# lamps.net
KiCad netlist of a schematic drawn in EAGLE
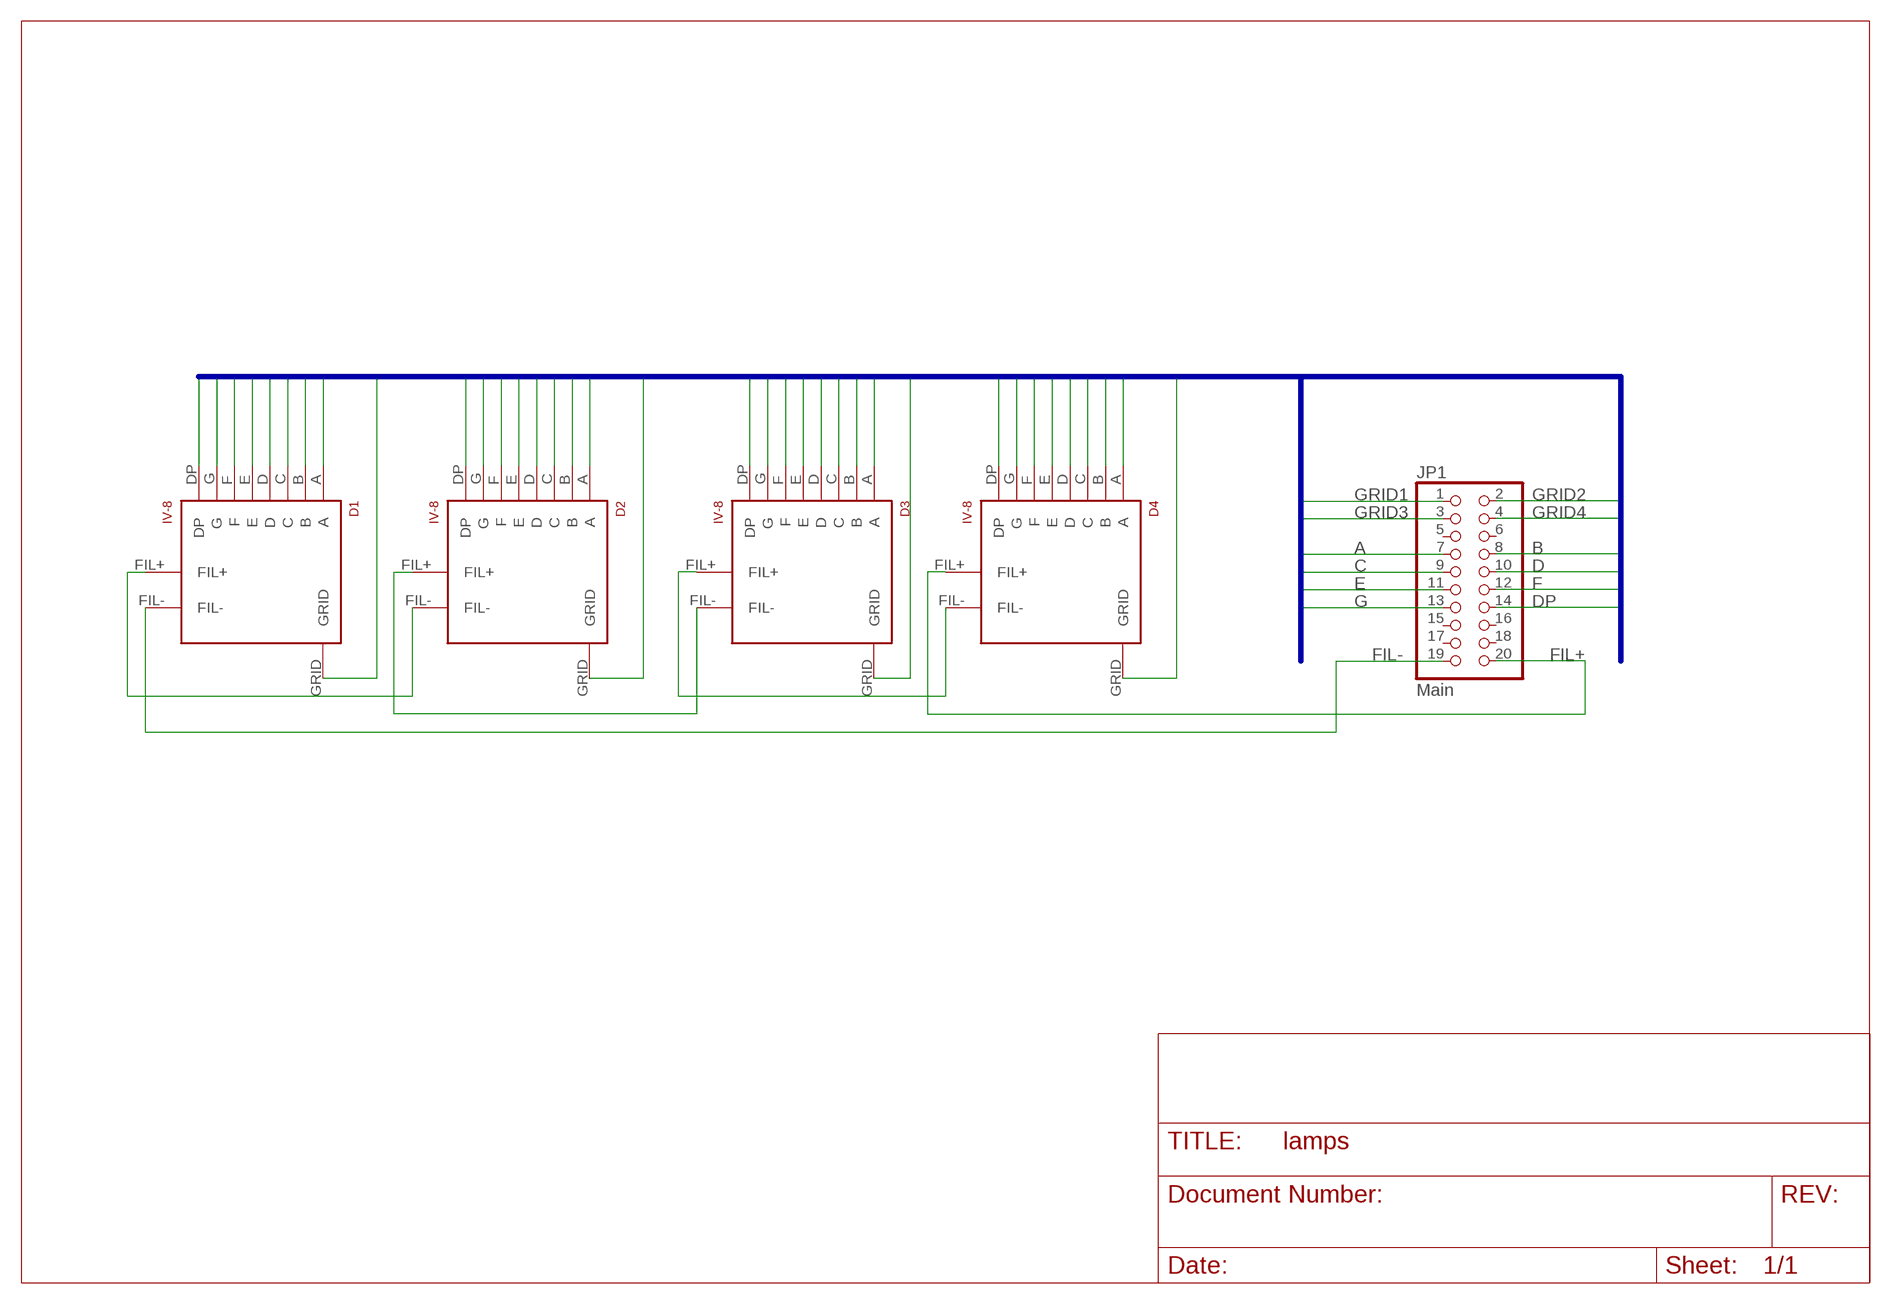
[diagram p0: schematic, sheet 1]

(export (version "E")
  (design (tool "Eeschema 10.0.6"))
  (components
    (comp (ref "D1")
      (value "IV-8")
      (footprint "eagle-import:IV-8")
      (libsource (lib "eagle-import") (part "IV-8"))
    )
    (comp (ref "D2")
      (value "IV-8")
      (footprint "eagle-import:IV-8")
      (libsource (lib "eagle-import") (part "IV-8"))
    )
    (comp (ref "D3")
      (value "IV-8")
      (footprint "eagle-import:IV-8")
      (libsource (lib "eagle-import") (part "IV-8"))
    )
    (comp (ref "D4")
      (value "IV-8")
      (footprint "eagle-import:IV-8")
      (libsource (lib "eagle-import") (part "IV-8"))
    )
    (comp (ref "JP1")
      (value "Main")
      (footprint "eagle-import:2X10")
      (libsource (lib "eagle-import") (part "PINHD-2X10"))
    )
  )
  (nets
    (net (code "1") (name "/A") (class "Default")
      (node (ref "D1") (pin "A") (pinfunction "A_A") (pintype "input"))
      (node (ref "D2") (pin "A") (pinfunction "A_A") (pintype "input"))
      (node (ref "D3") (pin "A") (pinfunction "A_A") (pintype "input"))
      (node (ref "D4") (pin "A") (pinfunction "A_A") (pintype "input"))
      (node (ref "JP1") (pin "7") (pinfunction "A_7") (pintype "passive"))
    )
    (net (code "2") (name "/B") (class "Default")
      (node (ref "D1") (pin "B") (pinfunction "B_B") (pintype "input"))
      (node (ref "D2") (pin "B") (pinfunction "B_B") (pintype "input"))
      (node (ref "D3") (pin "B") (pinfunction "B_B") (pintype "input"))
      (node (ref "D4") (pin "B") (pinfunction "B_B") (pintype "input"))
      (node (ref "JP1") (pin "8") (pinfunction "B_8") (pintype "passive"))
    )
    (net (code "3") (name "/C") (class "Default")
      (node (ref "D1") (pin "C") (pinfunction "C_C") (pintype "bidirectional"))
      (node (ref "D2") (pin "C") (pinfunction "C_C") (pintype "bidirectional"))
      (node (ref "D3") (pin "C") (pinfunction "C_C") (pintype "bidirectional"))
      (node (ref "D4") (pin "C") (pinfunction "C_C") (pintype "bidirectional"))
      (node (ref "JP1") (pin "9") (pinfunction "C_9") (pintype "passive"))
    )
    (net (code "4") (name "/D") (class "Default")
      (node (ref "D1") (pin "D") (pinfunction "D_D") (pintype "input"))
      (node (ref "D2") (pin "D") (pinfunction "D_D") (pintype "input"))
      (node (ref "D3") (pin "D") (pinfunction "D_D") (pintype "input"))
      (node (ref "D4") (pin "D") (pinfunction "D_D") (pintype "input"))
      (node (ref "JP1") (pin "10") (pinfunction "D_10") (pintype "passive"))
    )
    (net (code "5") (name "/DP") (class "Default")
      (node (ref "D1") (pin "DP") (pinfunction "DP_DP") (pintype "bidirectional"))
      (node (ref "D2") (pin "DP") (pinfunction "DP_DP") (pintype "bidirectional"))
      (node (ref "D3") (pin "DP") (pinfunction "DP_DP") (pintype "bidirectional"))
      (node (ref "D4") (pin "DP") (pinfunction "DP_DP") (pintype "bidirectional"))
      (node (ref "JP1") (pin "14") (pinfunction "DP_14") (pintype "passive"))
    )
    (net (code "6") (name "/E") (class "Default")
      (node (ref "D1") (pin "E") (pinfunction "E_E") (pintype "bidirectional"))
      (node (ref "D2") (pin "E") (pinfunction "E_E") (pintype "bidirectional"))
      (node (ref "D3") (pin "E") (pinfunction "E_E") (pintype "bidirectional"))
      (node (ref "D4") (pin "E") (pinfunction "E_E") (pintype "bidirectional"))
      (node (ref "JP1") (pin "11") (pinfunction "E_11") (pintype "passive"))
    )
    (net (code "7") (name "/F") (class "Default")
      (node (ref "D1") (pin "F") (pinfunction "F_F") (pintype "bidirectional"))
      (node (ref "D2") (pin "F") (pinfunction "F_F") (pintype "bidirectional"))
      (node (ref "D3") (pin "F") (pinfunction "F_F") (pintype "bidirectional"))
      (node (ref "D4") (pin "F") (pinfunction "F_F") (pintype "bidirectional"))
      (node (ref "JP1") (pin "12") (pinfunction "F_12") (pintype "passive"))
    )
    (net (code "8") (name "/FIL+") (class "Default")
      (node (ref "D4") (pin "FIL+") (pinfunction "FIL+_FIL+") (pintype "bidirectional"))
      (node (ref "JP1") (pin "20") (pinfunction "FIL+_20") (pintype "passive"))
    )
    (net (code "9") (name "/FIL-") (class "Default")
      (node (ref "D1") (pin "FIL-") (pinfunction "FIL-_FIL-") (pintype "bidirectional"))
      (node (ref "JP1") (pin "19") (pinfunction "FIL-_19") (pintype "passive"))
    )
    (net (code "10") (name "/G") (class "Default")
      (node (ref "D1") (pin "G") (pinfunction "G_G") (pintype "bidirectional"))
      (node (ref "D2") (pin "G") (pinfunction "G_G") (pintype "bidirectional"))
      (node (ref "D3") (pin "G") (pinfunction "G_G") (pintype "bidirectional"))
      (node (ref "D4") (pin "G") (pinfunction "G_G") (pintype "bidirectional"))
      (node (ref "JP1") (pin "13") (pinfunction "G_13") (pintype "passive"))
    )
    (net (code "11") (name "/GRID1") (class "Default")
      (node (ref "D1") (pin "GRID") (pinfunction "GRID_GRID") (pintype "input"))
      (node (ref "JP1") (pin "1") (pinfunction "GRID1_1") (pintype "passive"))
    )
    (net (code "12") (name "/GRID2") (class "Default")
      (node (ref "D2") (pin "GRID") (pinfunction "GRID_GRID") (pintype "input"))
      (node (ref "JP1") (pin "2") (pinfunction "GRID2_2") (pintype "passive"))
    )
    (net (code "13") (name "/GRID3") (class "Default")
      (node (ref "D3") (pin "GRID") (pinfunction "GRID_GRID") (pintype "input"))
      (node (ref "JP1") (pin "3") (pinfunction "GRID3_3") (pintype "passive"))
    )
    (net (code "14") (name "/GRID4") (class "Default")
      (node (ref "D4") (pin "GRID") (pinfunction "GRID_GRID") (pintype "input"))
      (node (ref "JP1") (pin "4") (pinfunction "GRID4_4") (pintype "passive"))
    )
    (net (code "15") (name "Net-(D1-PadFIL+)") (class "Default")
      (node (ref "D1") (pin "FIL+") (pinfunction "FIL+_FIL+") (pintype "bidirectional"))
      (node (ref "D2") (pin "FIL-") (pinfunction "FIL-_FIL-") (pintype "bidirectional"))
    )
    (net (code "16") (name "Net-(D2-PadFIL+)") (class "Default")
      (node (ref "D2") (pin "FIL+") (pinfunction "FIL+_FIL+") (pintype "bidirectional"))
      (node (ref "D3") (pin "FIL-") (pinfunction "FIL-_FIL-") (pintype "bidirectional"))
    )
    (net (code "17") (name "Net-(D3-PadFIL+)") (class "Default")
      (node (ref "D3") (pin "FIL+") (pinfunction "FIL+_FIL+") (pintype "bidirectional"))
      (node (ref "D4") (pin "FIL-") (pinfunction "FIL-_FIL-") (pintype "bidirectional"))
    )
    (net (code "18") (name "unconnected-(JP1-GRID5-Pad5)") (class "Default")
      (node (ref "JP1") (pin "5") (pinfunction "GRID5_5") (pintype "passive"))
    )
    (net (code "19") (name "unconnected-(JP1-GRID6-Pad6)") (class "Default")
      (node (ref "JP1") (pin "6") (pinfunction "GRID6_6") (pintype "passive"))
    )
    (net (code "20") (name "unconnected-(JP1-Pad15)") (class "Default")
      (node (ref "JP1") (pin "15") (pinfunction "15_15") (pintype "passive"))
    )
    (net (code "21") (name "unconnected-(JP1-Pad16)") (class "Default")
      (node (ref "JP1") (pin "16") (pinfunction "16_16") (pintype "passive"))
    )
    (net (code "22") (name "unconnected-(JP1-Pad17)") (class "Default")
      (node (ref "JP1") (pin "17") (pinfunction "17_17") (pintype "passive"))
    )
    (net (code "23") (name "unconnected-(JP1-Pad18)") (class "Default")
      (node (ref "JP1") (pin "18") (pinfunction "18_18") (pintype "passive"))
    )
  )
)
